# v2.net
KiCad netlist of a schematic drawn in Altium Designer
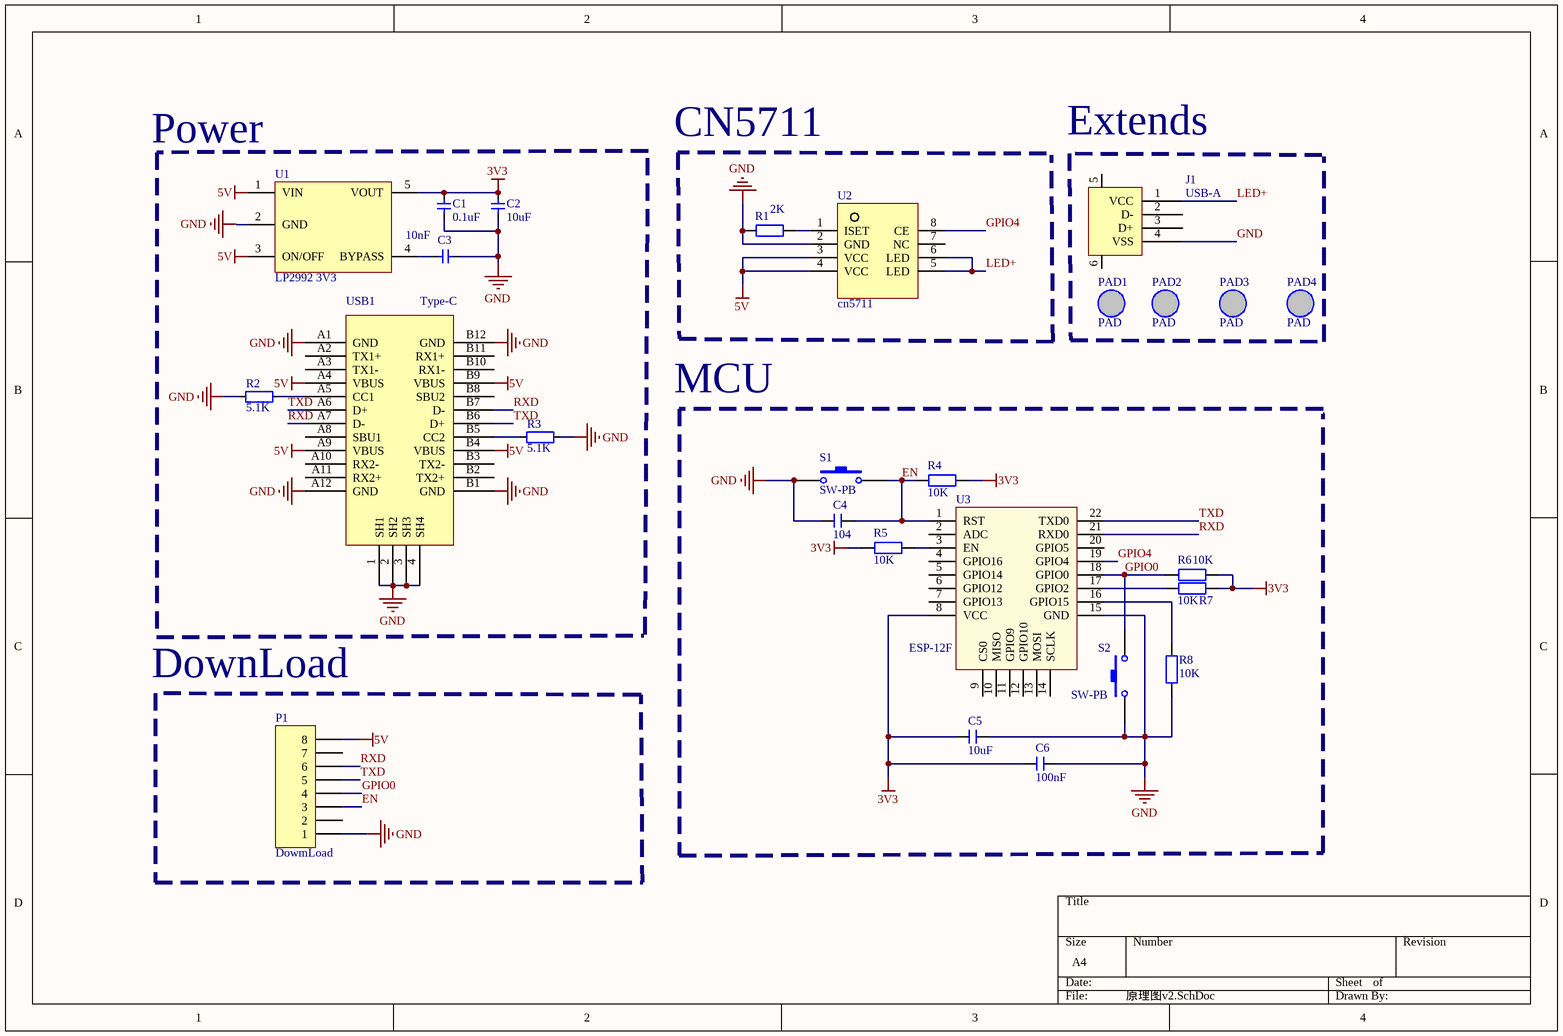
[diagram p0: 原理图v2.SchDoc]

(export (version "E")
  (design (tool "Eeschema 10.0.6"))
  (components
    (comp (ref "C1")
      (value "0.1uF")
      (footprint "CAP_0402")
      (description "Capacitor")
      (libsource (lib "MyPcbLib") (part "电容-0402"))
    )
    (comp (ref "C2")
      (value "10uF")
      (footprint "C0805_L")
      (description "Capacitor")
      (libsource (lib "MyPcbLib") (part "电容-0402"))
    )
    (comp (ref "C3")
      (value "10nF")
      (footprint "CAP_0402")
      (description "Capacitor")
      (libsource (lib "MyPcbLib") (part "电容-0402"))
    )
    (comp (ref "C4")
      (value "104")
      (footprint "CAP_0402")
      (description "无极性贴片电容")
      (fields (field (name "版权归属") "源创客"))
      (libsource (lib "9-电阻-电容-电感") (part "C"))
    )
    (comp (ref "C5")
      (value "10uF")
      (footprint "C0805_L")
      (description "无极性贴片电容")
      (fields (field (name "版权归属") "源创客"))
      (libsource (lib "9-电阻-电容-电感") (part "C"))
    )
    (comp (ref "C6")
      (value "100nF")
      (footprint "CAP_0402")
      (description "无极性贴片电容")
      (fields (field (name "版权归属") "源创客"))
      (libsource (lib "9-电阻-电容-电感") (part "C"))
    )
    (comp (ref "J1")
      (value "USB-A")
      (footprint "USB-A/S_C")
      (description "USB接口")
      (libsource (lib "18-常用器件") (part "USB"))
    )
    (comp (ref "P1")
      (value "DowmLoad")
      (footprint "FPC0.5 2H-WS-8P")
      (description "Header, 8-Pin")
      (fields (field (name "PUBLISHER") "Altium Limited"))
      (libsource (lib "Miscellaneous Connectors") (part "Header 8"))
    )
    (comp (ref "PAD1")
      (value "PAD")
      (footprint "M2")
      (description "M2通孔")
      (libsource (lib "原理图库") (part "PAD"))
    )
    (comp (ref "PAD2")
      (value "PAD")
      (footprint "M2")
      (description "M2通孔")
      (libsource (lib "原理图库") (part "PAD"))
    )
    (comp (ref "PAD3")
      (value "PAD")
      (footprint "M2")
      (description "M2通孔")
      (libsource (lib "原理图库") (part "PAD"))
    )
    (comp (ref "PAD4")
      (value "PAD")
      (footprint "M2")
      (description "M2通孔")
      (libsource (lib "原理图库") (part "PAD"))
    )
    (comp (ref "R1")
      (value "2K")
      (footprint "RES_0402")
      (description "贴片电阻")
      (fields (field (name "版权归属") "源创客"))
      (libsource (lib "9-电阻-电容-电感") (part "R"))
    )
    (comp (ref "R2")
      (value "5.1K")
      (footprint "RES_0402")
      (description "Resistor")
      (libsource (lib "") (part "电阻-0402_1"))
    )
    (comp (ref "R3")
      (value "5.1K")
      (footprint "RES_0402")
      (description "Resistor")
      (libsource (lib "MyPcbLib") (part "电阻-0402"))
    )
    (comp (ref "R4")
      (value "10K")
      (footprint "RES_0402")
      (description "贴片电阻")
      (fields (field (name "版权归属") "源创客"))
      (libsource (lib "9-电阻-电容-电感") (part "R"))
    )
    (comp (ref "R5")
      (value "10K")
      (footprint "RES_0402")
      (description "贴片电阻")
      (fields (field (name "版权归属") "源创客"))
      (libsource (lib "9-电阻-电容-电感") (part "R"))
    )
    (comp (ref "R6")
      (value "10K")
      (footprint "RES_0402")
      (description "贴片电阻")
      (fields (field (name "版权归属") "源创客"))
      (libsource (lib "9-电阻-电容-电感") (part "R"))
    )
    (comp (ref "R7")
      (value "10K")
      (footprint "RES_0402")
      (description "贴片电阻")
      (fields (field (name "版权归属") "源创客"))
      (libsource (lib "9-电阻-电容-电感") (part "R"))
    )
    (comp (ref "R8")
      (value "10K")
      (footprint "RES_0402")
      (description "贴片电阻")
      (fields (field (name "版权归属") "源创客"))
      (libsource (lib "9-电阻-电容-电感") (part "R"))
    )
    (comp (ref "S1")
      (value "SW-PB")
      (footprint "SW SMD-3*6*2.5")
      (description "微动开关")
      (fields (field (name "PUBLISHER") "Altium Limited"))
      (libsource (lib "18-常用器件") (part "SW-PB"))
    )
    (comp (ref "S2")
      (value "SW-PB")
      (footprint "SW SMD-3*6*2.5")
      (description "微动开关")
      (fields (field (name "PUBLISHER") "Altium Limited"))
      (libsource (lib "18-常用器件") (part "SW-PB"))
    )
    (comp (ref "U1")
      (value "LP2992 3V3")
      (footprint "SOT23-5")
      (description "LDO")
      (libsource (lib "MyPcbLib") (part "LP2992"))
    )
    (comp (ref "U2") (value "cn5711") (footprint "SOP8") (libsource (lib "esp8266项目原理图库") (part "cn5711")))
    (comp (ref "U3")
      (value "ESP-12F")
      (footprint "ESP-12F")
      (fields (field (name "MANUFACTURER") "安信可"))
      (libsource (lib "其他") (part "ESP-12F"))
    )
    (comp (ref "USB1")
      (value "Type-C")
      (footprint "USB-C-SMD_16P")
      (libsource (lib "MyPcbLib") (part "USB-Type-C-TOP"))
    )
  )
  (nets
    (net (code "1") (name "/EN") (class "Default")
      (node (ref "C4") (pin "2") (pinfunction "2_2") (pintype "passive"))
      (node (ref "P1") (pin "3") (pinfunction "3_3") (pintype "passive"))
      (node (ref "R4") (pin "1") (pinfunction "1_1") (pintype "passive"))
      (node (ref "S1") (pin "2") (pinfunction "2_2") (pintype "passive"))
      (node (ref "U3") (pin "1") (pinfunction "RST_1") (pintype "passive"))
    )
    (net (code "2") (name "/GPIO0") (class "Default")
      (node (ref "P1") (pin "4") (pinfunction "4_4") (pintype "passive"))
      (node (ref "R6") (pin "1") (pinfunction "1_1") (pintype "passive"))
      (node (ref "S2") (pin "2") (pinfunction "2_2") (pintype "passive"))
      (node (ref "U3") (pin "18") (pinfunction "GPIO0_18") (pintype "passive"))
    )
    (net (code "3") (name "/GPIO4") (class "Default")
      (node (ref "U2") (pin "8") (pinfunction "CE_8") (pintype "passive"))
      (node (ref "U3") (pin "19") (pinfunction "GPIO4_19") (pintype "passive"))
    )
    (net (code "4") (name "/LED+") (class "Default")
      (node (ref "J1") (pin "1") (pinfunction "VCC_1") (pintype "passive"))
      (node (ref "U2") (pin "5") (pinfunction "LED_5") (pintype "passive"))
      (node (ref "U2") (pin "6") (pinfunction "LED_6") (pintype "passive"))
    )
    (net (code "5") (name "/RXD") (class "Default")
      (node (ref "P1") (pin "6") (pinfunction "6_6") (pintype "passive"))
      (node (ref "U3") (pin "21") (pinfunction "RXD0_21") (pintype "passive"))
      (node (ref "USB1") (pin "A7") (pinfunction "D-_A7") (pintype "passive"))
      (node (ref "USB1") (pin "B7") (pinfunction "D-_B7") (pintype "passive"))
    )
    (net (code "6") (name "/TXD") (class "Default")
      (node (ref "P1") (pin "5") (pinfunction "5_5") (pintype "passive"))
      (node (ref "U3") (pin "22") (pinfunction "TXD0_22") (pintype "passive"))
      (node (ref "USB1") (pin "A6") (pinfunction "D+_A6") (pintype "passive"))
      (node (ref "USB1") (pin "B6") (pinfunction "D+_B6") (pintype "passive"))
    )
    (net (code "7") (name "3V3") (class "Default")
      (node (ref "C1") (pin "2") (pinfunction "2_2") (pintype "passive"))
      (node (ref "C2") (pin "2") (pinfunction "2_2") (pintype "passive"))
      (node (ref "C5") (pin "1") (pinfunction "1_1") (pintype "passive"))
      (node (ref "C6") (pin "1") (pinfunction "1_1") (pintype "passive"))
      (node (ref "R4") (pin "2") (pinfunction "2_2") (pintype "passive"))
      (node (ref "R5") (pin "1") (pinfunction "1_1") (pintype "passive"))
      (node (ref "R6") (pin "2") (pinfunction "2_2") (pintype "passive"))
      (node (ref "R7") (pin "2") (pinfunction "2_2") (pintype "passive"))
      (node (ref "U1") (pin "5") (pinfunction "VOUT_5") (pintype "passive"))
      (node (ref "U3") (pin "8") (pinfunction "VCC_8") (pintype "passive"))
    )
    (net (code "8") (name "5V") (class "Default")
      (node (ref "P1") (pin "8") (pinfunction "8_8") (pintype "passive"))
      (node (ref "U1") (pin "1") (pinfunction "VIN_1") (pintype "passive"))
      (node (ref "U1") (pin "3") (pinfunction "ON/OFF_3") (pintype "passive"))
      (node (ref "U2") (pin "3") (pinfunction "VCC_3") (pintype "passive"))
      (node (ref "U2") (pin "4") (pinfunction "VCC_4") (pintype "passive"))
      (node (ref "USB1") (pin "A4") (pinfunction "VBUS_A4") (pintype "passive"))
      (node (ref "USB1") (pin "A9") (pinfunction "VBUS_A9") (pintype "passive"))
      (node (ref "USB1") (pin "B4") (pinfunction "VBUS_B4") (pintype "passive"))
      (node (ref "USB1") (pin "B9") (pinfunction "VBUS_B9") (pintype "passive"))
    )
    (net (code "9") (name "GND") (class "Default")
      (node (ref "C1") (pin "1") (pinfunction "1_1") (pintype "passive"))
      (node (ref "C2") (pin "1") (pinfunction "1_1") (pintype "passive"))
      (node (ref "C3") (pin "1") (pinfunction "1_1") (pintype "passive"))
      (node (ref "C4") (pin "1") (pinfunction "1_1") (pintype "passive"))
      (node (ref "C5") (pin "2") (pinfunction "2_2") (pintype "passive"))
      (node (ref "C6") (pin "2") (pinfunction "2_2") (pintype "passive"))
      (node (ref "J1") (pin "4") (pinfunction "VSS_4") (pintype "passive"))
      (node (ref "P1") (pin "1") (pinfunction "1_1") (pintype "passive"))
      (node (ref "R1") (pin "1") (pinfunction "1_1") (pintype "passive"))
      (node (ref "R2") (pin "1") (pinfunction "1_1") (pintype "passive"))
      (node (ref "R3") (pin "1") (pinfunction "1_1") (pintype "passive"))
      (node (ref "R8") (pin "1") (pinfunction "1_1") (pintype "passive"))
      (node (ref "S1") (pin "1") (pinfunction "1_1") (pintype "passive"))
      (node (ref "S2") (pin "1") (pinfunction "1_1") (pintype "passive"))
      (node (ref "U1") (pin "2") (pinfunction "GND_2") (pintype "passive"))
      (node (ref "U2") (pin "2") (pinfunction "GND_2") (pintype "passive"))
      (node (ref "U3") (pin "15") (pinfunction "GND_15") (pintype "passive"))
      (node (ref "USB1") (pin "1") (pinfunction "SH1_1") (pintype "passive"))
      (node (ref "USB1") (pin "2") (pinfunction "SH2_2") (pintype "passive"))
      (node (ref "USB1") (pin "3") (pinfunction "SH3_3") (pintype "passive"))
      (node (ref "USB1") (pin "4") (pinfunction "SH4_4") (pintype "passive"))
      (node (ref "USB1") (pin "A1") (pinfunction "GND_A1") (pintype "passive"))
      (node (ref "USB1") (pin "A12") (pinfunction "GND_A12") (pintype "passive"))
      (node (ref "USB1") (pin "B1") (pinfunction "GND_B1") (pintype "passive"))
      (node (ref "USB1") (pin "B12") (pinfunction "GND_B12") (pintype "passive"))
    )
    (net (code "10") (name "Net-(U1-BYPASS)") (class "Default")
      (node (ref "C3") (pin "2") (pinfunction "2_2") (pintype "passive"))
      (node (ref "U1") (pin "4") (pinfunction "BYPASS_4") (pintype "passive"))
    )
    (net (code "11") (name "Net-(U2-ISET)") (class "Default")
      (node (ref "R1") (pin "2") (pinfunction "2_2") (pintype "passive"))
      (node (ref "U2") (pin "1") (pinfunction "ISET_1") (pintype "passive"))
    )
    (net (code "12") (name "Net-(U3-EN)") (class "Default")
      (node (ref "R5") (pin "2") (pinfunction "2_2") (pintype "passive"))
      (node (ref "U3") (pin "3") (pinfunction "EN_3") (pintype "passive"))
    )
    (net (code "13") (name "Net-(U3-GPIO2)") (class "Default")
      (node (ref "R7") (pin "1") (pinfunction "1_1") (pintype "passive"))
      (node (ref "U3") (pin "17") (pinfunction "GPIO2_17") (pintype "passive"))
    )
    (net (code "14") (name "Net-(U3-GPIO15)") (class "Default")
      (node (ref "R8") (pin "2") (pinfunction "2_2") (pintype "passive"))
      (node (ref "U3") (pin "16") (pinfunction "GPIO15_16") (pintype "passive"))
    )
    (net (code "15") (name "Net-(USB1-CC1)") (class "Default")
      (node (ref "R2") (pin "2") (pinfunction "2_2") (pintype "passive"))
      (node (ref "USB1") (pin "A5") (pinfunction "CC1_A5") (pintype "passive"))
    )
    (net (code "16") (name "Net-(USB1-CC2)") (class "Default")
      (node (ref "R3") (pin "2") (pinfunction "2_2") (pintype "passive"))
      (node (ref "USB1") (pin "B5") (pinfunction "CC2_B5") (pintype "passive"))
    )
    (net (code "17") (name "unconnected-(J1-D+-Pad3)") (class "Default")
      (node (ref "J1") (pin "3") (pinfunction "D+_3") (pintype "passive"))
    )
    (net (code "18") (name "unconnected-(J1-D--Pad2)") (class "Default")
      (node (ref "J1") (pin "2") (pinfunction "D-_2") (pintype "passive"))
    )
    (net (code "19") (name "unconnected-(J1-Pad5)") (class "Default")
      (node (ref "J1") (pin "5") (pinfunction "5_5") (pintype "passive"))
    )
    (net (code "20") (name "unconnected-(J1-Pad6)") (class "Default")
      (node (ref "J1") (pin "6") (pinfunction "6_6") (pintype "passive"))
    )
    (net (code "21") (name "unconnected-(P1-Pad2)") (class "Default")
      (node (ref "P1") (pin "2") (pinfunction "2_2") (pintype "passive"))
    )
    (net (code "22") (name "unconnected-(P1-Pad7)") (class "Default")
      (node (ref "P1") (pin "7") (pinfunction "7_7") (pintype "passive"))
    )
    (net (code "23") (name "unconnected-(U2-NC-Pad7)") (class "Default")
      (node (ref "U2") (pin "7") (pinfunction "NC_7") (pintype "passive"))
    )
    (net (code "24") (name "unconnected-(U3-ADC-Pad2)") (class "Default")
      (node (ref "U3") (pin "2") (pinfunction "ADC_2") (pintype "passive"))
    )
    (net (code "25") (name "unconnected-(U3-CS0-Pad9)") (class "Default")
      (node (ref "U3") (pin "9") (pinfunction "CS0_9") (pintype "passive"))
    )
    (net (code "26") (name "unconnected-(U3-GPIO5-Pad20)") (class "Default")
      (node (ref "U3") (pin "20") (pinfunction "GPIO5_20") (pintype "passive"))
    )
    (net (code "27") (name "unconnected-(U3-GPIO9-Pad11)") (class "Default")
      (node (ref "U3") (pin "11") (pinfunction "GPIO9_11") (pintype "passive"))
    )
    (net (code "28") (name "unconnected-(U3-GPIO10-Pad12)") (class "Default")
      (node (ref "U3") (pin "12") (pinfunction "GPIO10_12") (pintype "passive"))
    )
    (net (code "29") (name "unconnected-(U3-GPIO12-Pad6)") (class "Default")
      (node (ref "U3") (pin "6") (pinfunction "GPIO12_6") (pintype "passive"))
    )
    (net (code "30") (name "unconnected-(U3-GPIO13-Pad7)") (class "Default")
      (node (ref "U3") (pin "7") (pinfunction "GPIO13_7") (pintype "passive"))
    )
    (net (code "31") (name "unconnected-(U3-GPIO14-Pad5)") (class "Default")
      (node (ref "U3") (pin "5") (pinfunction "GPIO14_5") (pintype "passive"))
    )
    (net (code "32") (name "unconnected-(U3-GPIO16-Pad4)") (class "Default")
      (node (ref "U3") (pin "4") (pinfunction "GPIO16_4") (pintype "passive"))
    )
    (net (code "33") (name "unconnected-(U3-MISO-Pad10)") (class "Default")
      (node (ref "U3") (pin "10") (pinfunction "MISO_10") (pintype "passive"))
    )
    (net (code "34") (name "unconnected-(U3-MOSI-Pad13)") (class "Default")
      (node (ref "U3") (pin "13") (pinfunction "MOSI_13") (pintype "passive"))
    )
    (net (code "35") (name "unconnected-(U3-SCLK-Pad14)") (class "Default")
      (node (ref "U3") (pin "14") (pinfunction "SCLK_14") (pintype "passive"))
    )
    (net (code "36") (name "unconnected-(USB1-RX1+-PadB11)") (class "Default")
      (node (ref "USB1") (pin "B11") (pinfunction "RX1+_B11") (pintype "passive"))
    )
    (net (code "37") (name "unconnected-(USB1-RX1--PadB10)") (class "Default")
      (node (ref "USB1") (pin "B10") (pinfunction "RX1-_B10") (pintype "passive"))
    )
    (net (code "38") (name "unconnected-(USB1-RX2+-PadA11)") (class "Default")
      (node (ref "USB1") (pin "A11") (pinfunction "RX2+_A11") (pintype "passive"))
    )
    (net (code "39") (name "unconnected-(USB1-RX2--PadA10)") (class "Default")
      (node (ref "USB1") (pin "A10") (pinfunction "RX2-_A10") (pintype "passive"))
    )
    (net (code "40") (name "unconnected-(USB1-SBU1-PadA8)") (class "Default")
      (node (ref "USB1") (pin "A8") (pinfunction "SBU1_A8") (pintype "passive"))
    )
    (net (code "41") (name "unconnected-(USB1-SBU2-PadB8)") (class "Default")
      (node (ref "USB1") (pin "B8") (pinfunction "SBU2_B8") (pintype "passive"))
    )
    (net (code "42") (name "unconnected-(USB1-TX1+-PadA2)") (class "Default")
      (node (ref "USB1") (pin "A2") (pinfunction "TX1+_A2") (pintype "passive"))
    )
    (net (code "43") (name "unconnected-(USB1-TX1--PadA3)") (class "Default")
      (node (ref "USB1") (pin "A3") (pinfunction "TX1-_A3") (pintype "passive"))
    )
    (net (code "44") (name "unconnected-(USB1-TX2+-PadB2)") (class "Default")
      (node (ref "USB1") (pin "B2") (pinfunction "TX2+_B2") (pintype "passive"))
    )
    (net (code "45") (name "unconnected-(USB1-TX2--PadB3)") (class "Default")
      (node (ref "USB1") (pin "B3") (pinfunction "TX2-_B3") (pintype "passive"))
    )
  )
)
